# bicyclelab-charger-4_1.net
KiCad netlist of a schematic drawn in EAGLE
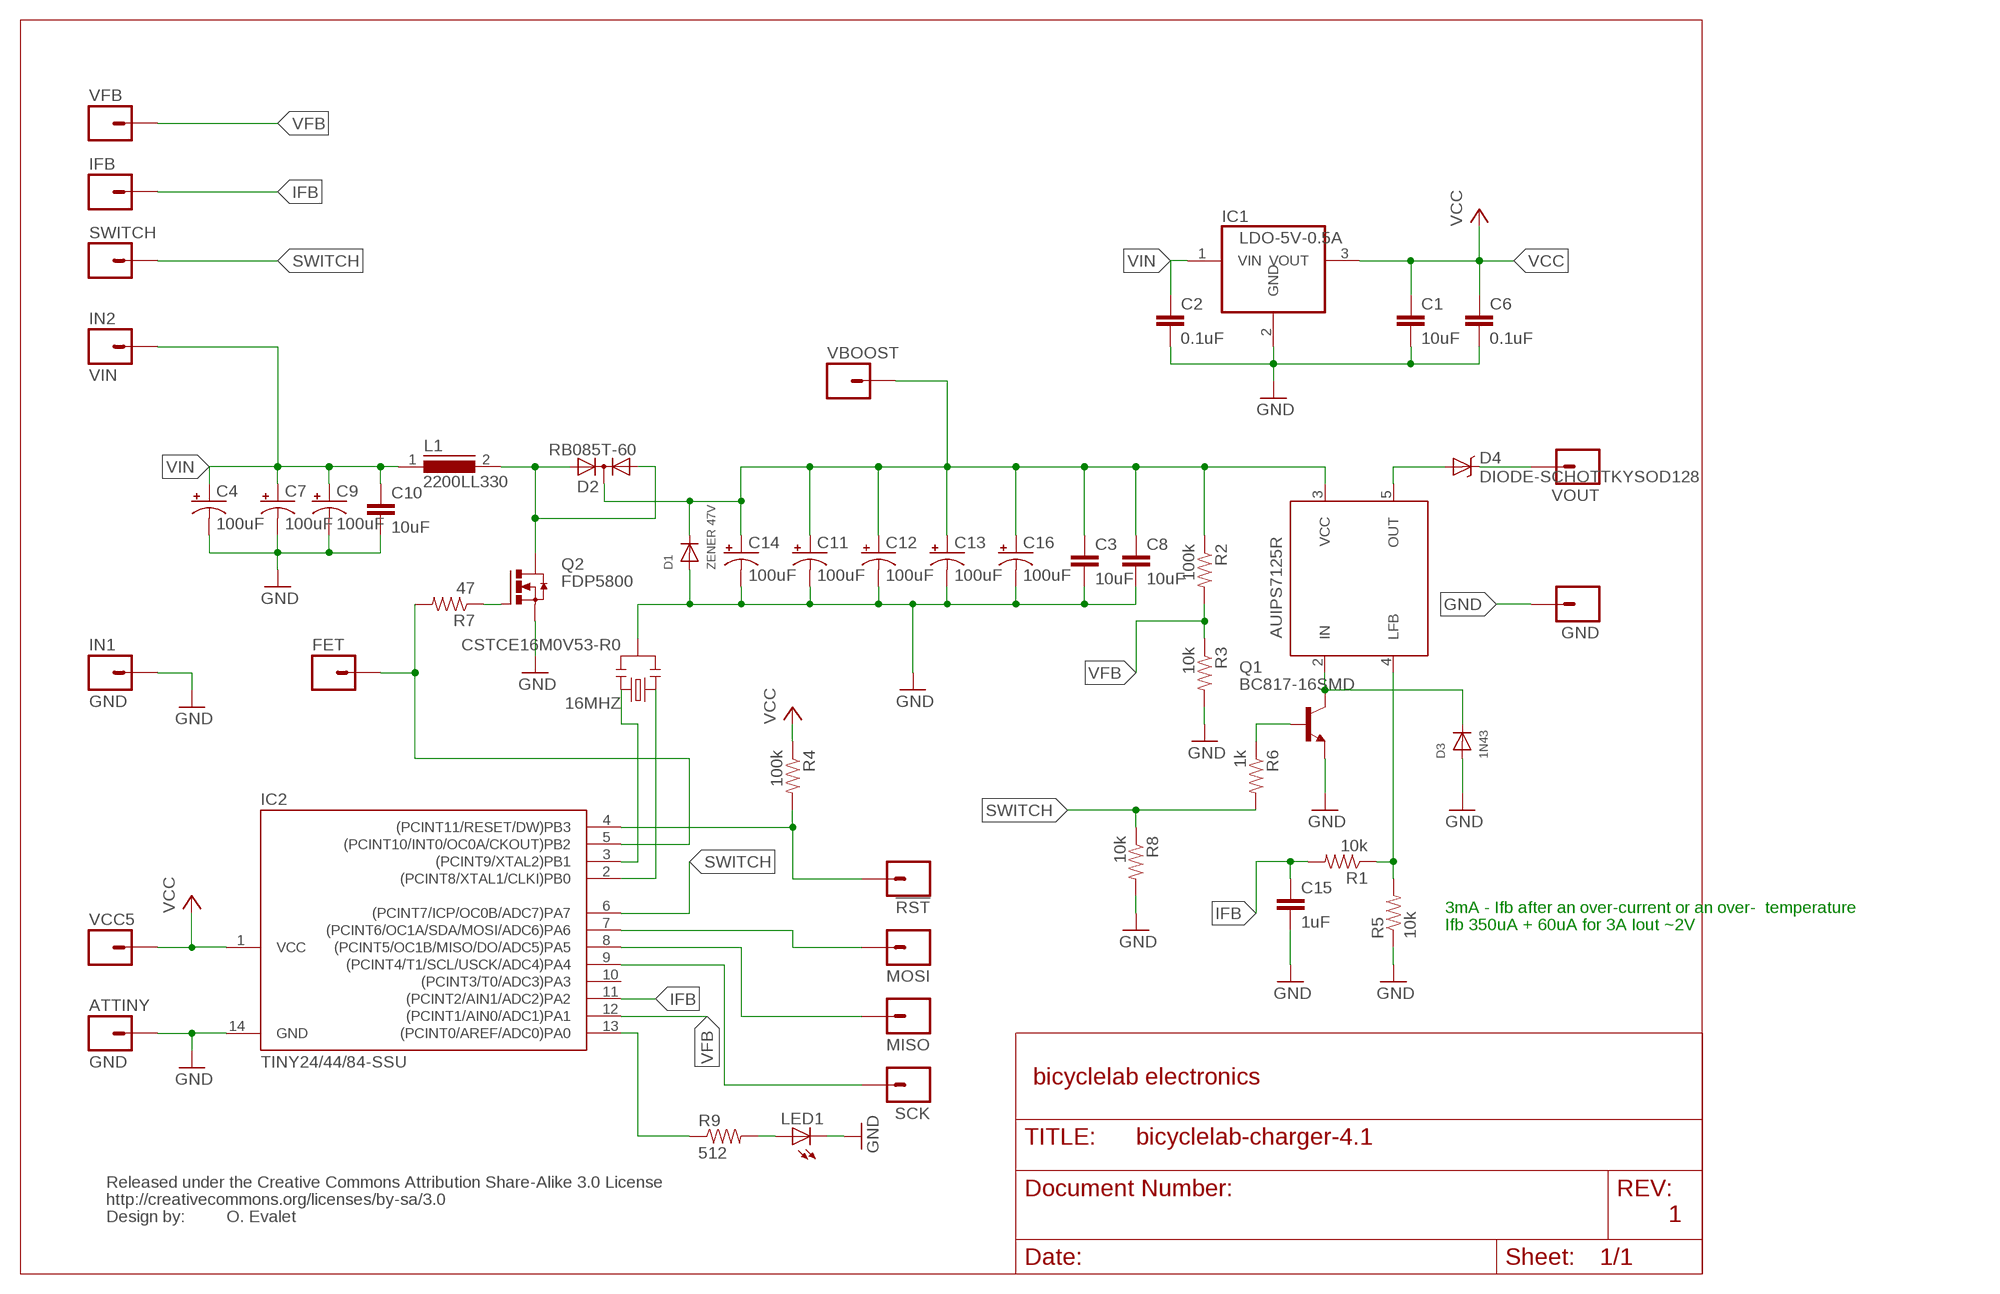
[diagram p0: schematic, sheet 1]

(export (version "E")
  (design (tool "Eeschema 10.0.6"))
  (components
    (comp (ref "!RST")
      (value "M01SMDNS")
      (footprint "eagle-import:1X01NS")
      (libsource (lib "eagle-import") (part "M01SMDNS"))
    )
    (comp (ref "16MHZ")
      (value "CSTCE16M0V53-R0")
      (footprint "eagle-import:RESONATOR-SMD")
      (libsource (lib "eagle-import") (part "RESONATORSMD"))
    )
    (comp (ref "ATTINY")
      (value "GND")
      (footprint "eagle-import:1X01NS")
      (libsource (lib "eagle-import") (part "M01SMDNS"))
    )
    (comp (ref "C1")
      (value "10uF")
      (footprint "eagle-import:0805")
      (libsource (lib "eagle-import") (part "bicyclelab_CAP0805"))
    )
    (comp (ref "C2")
      (value "0.1uF")
      (footprint "eagle-import:0805")
      (libsource (lib "eagle-import") (part "CAP0805"))
    )
    (comp (ref "C3")
      (value "10uF")
      (footprint "eagle-import:1210")
      (libsource (lib "eagle-import") (part "CAP1210"))
    )
    (comp (ref "C4")
      (value "100uF")
      (footprint "eagle-import:PANASONIC_D")
      (libsource (lib "eagle-import") (part "CPOL-USD"))
    )
    (comp (ref "C6")
      (value "0.1uF")
      (footprint "eagle-import:0805")
      (libsource (lib "eagle-import") (part "CAP0805"))
    )
    (comp (ref "C7")
      (value "100uF")
      (footprint "eagle-import:PANASONIC_D")
      (libsource (lib "eagle-import") (part "CPOL-USD"))
    )
    (comp (ref "C8")
      (value "10uF")
      (footprint "eagle-import:1210")
      (libsource (lib "eagle-import") (part "CAP1210"))
    )
    (comp (ref "C9")
      (value "100uF")
      (footprint "eagle-import:PANASONIC_D")
      (libsource (lib "eagle-import") (part "CPOL-USD"))
    )
    (comp (ref "C10")
      (value "10uF")
      (footprint "eagle-import:1210")
      (libsource (lib "eagle-import") (part "CAP1210"))
    )
    (comp (ref "C11")
      (value "100uF")
      (footprint "eagle-import:PANASONIC_D")
      (libsource (lib "eagle-import") (part "CPOL-USD"))
    )
    (comp (ref "C12")
      (value "100uF")
      (footprint "eagle-import:PANASONIC_D")
      (libsource (lib "eagle-import") (part "CPOL-USD"))
    )
    (comp (ref "C13")
      (value "100uF")
      (footprint "eagle-import:PANASONIC_D")
      (libsource (lib "eagle-import") (part "CPOL-USD"))
    )
    (comp (ref "C14")
      (value "100uF")
      (footprint "eagle-import:PANASONIC_D")
      (libsource (lib "eagle-import") (part "CPOL-USD"))
    )
    (comp (ref "C15")
      (value "1uF")
      (footprint "eagle-import:0805")
      (libsource (lib "eagle-import") (part "CAP0805"))
    )
    (comp (ref "C16")
      (value "100uF")
      (footprint "eagle-import:PANASONIC_D")
      (libsource (lib "eagle-import") (part "CPOL-USD"))
    )
    (comp (ref "D1")
      (value "ZENER 47V")
      (footprint "eagle-import:SOD-123")
      (libsource (lib "eagle-import") (part "DIODESOD-123"))
    )
    (comp (ref "D2")
      (value "RB085T-60")
      (footprint "eagle-import:TO220AB")
      (libsource (lib "eagle-import") (part "DIODE-2AC|CATO220H"))
    )
    (comp (ref "D3")
      (value "1N43")
      (footprint "eagle-import:SOD-123")
      (libsource (lib "eagle-import") (part "DIODESOD-123"))
    )
    (comp (ref "D4")
      (value "DIODE-SCHOTTKYSOD128")
      (footprint "eagle-import:SOD-128")
      (libsource (lib "eagle-import") (part "DIODE-SCHOTTKYSOD128"))
    )
    (comp (ref "FET")
      (value "M01SMDNS")
      (footprint "eagle-import:1X01NS")
      (libsource (lib "eagle-import") (part "M01SMDNS"))
    )
    (comp (ref "GND")
      (value "M01SMDNS")
      (footprint "eagle-import:1X01NS")
      (libsource (lib "eagle-import") (part "M01SMDNS"))
    )
    (comp (ref "IC1")
      (value "LDO-5V-0.5A")
      (footprint "eagle-import:SOT223")
      (libsource (lib "eagle-import") (part "LDO-5V-0.5A"))
    )
    (comp (ref "IC2")
      (value "TINY24/44/84-SSU")
      (footprint "eagle-import:SOIC14")
      (libsource (lib "eagle-import") (part "TINY24/44/84-SSU"))
    )
    (comp (ref "IFB")
      (value "M01SMDNS")
      (footprint "eagle-import:1X01NS")
      (libsource (lib "eagle-import") (part "M01SMDNS"))
    )
    (comp (ref "IN1")
      (value "GND")
      (footprint "eagle-import:1X01NS")
      (libsource (lib "eagle-import") (part "M01SMDNS"))
    )
    (comp (ref "IN2")
      (value "VIN")
      (footprint "eagle-import:1X01")
      (libsource (lib "eagle-import") (part "M01PTH"))
    )
    (comp (ref "L1")
      (value "2200LL330")
      (footprint "eagle-import:DR175")
      (libsource (lib "eagle-import") (part "DR175"))
    )
    (comp (ref "LED1")
      (value "LEDCHIP-LED0805")
      (footprint "eagle-import:CHIP-LED0805")
      (libsource (lib "eagle-import") (part "LEDCHIP-LED0805"))
    )
    (comp (ref "MISO")
      (value "M01SMDNS")
      (footprint "eagle-import:1X01NS")
      (libsource (lib "eagle-import") (part "M01SMDNS"))
    )
    (comp (ref "MOSI")
      (value "M01SMDNS")
      (footprint "eagle-import:1X01NS")
      (libsource (lib "eagle-import") (part "M01SMDNS"))
    )
    (comp (ref "Q1")
      (value "BC817-16SMD")
      (footprint "eagle-import:SOT23-BEC")
      (libsource (lib "eagle-import") (part "BC817SMD-16"))
    )
    (comp (ref "Q2")
      (value "FDP5800")
      (footprint "eagle-import:TO220AH")
      (libsource (lib "eagle-import") (part "IRF3704"))
    )
    (comp (ref "R1")
      (value "10k")
      (footprint "eagle-import:0805")
      (libsource (lib "eagle-import") (part "RESISTOR"))
    )
    (comp (ref "R2")
      (value "100k")
      (footprint "eagle-import:0805")
      (libsource (lib "eagle-import") (part "RESISTOR"))
    )
    (comp (ref "R3")
      (value "10k")
      (footprint "eagle-import:0805")
      (libsource (lib "eagle-import") (part "RESISTOR"))
    )
    (comp (ref "R4")
      (value "100k")
      (footprint "eagle-import:0805")
      (libsource (lib "eagle-import") (part "RESISTOR"))
    )
    (comp (ref "R5")
      (value "10k")
      (footprint "eagle-import:0805")
      (libsource (lib "eagle-import") (part "RESISTOR"))
    )
    (comp (ref "R6")
      (value "1k")
      (footprint "eagle-import:0805")
      (libsource (lib "eagle-import") (part "RESISTOR"))
    )
    (comp (ref "R7")
      (value "47")
      (footprint "eagle-import:0805")
      (libsource (lib "eagle-import") (part "RESISTOR"))
    )
    (comp (ref "R8")
      (value "10k")
      (footprint "eagle-import:0805")
      (libsource (lib "eagle-import") (part "RESISTOR"))
    )
    (comp (ref "R9")
      (value "512")
      (footprint "eagle-import:0805")
      (libsource (lib "eagle-import") (part "RESISTOR"))
    )
    (comp (ref "SCK")
      (value "M01SMDNS")
      (footprint "eagle-import:1X01NS")
      (libsource (lib "eagle-import") (part "M01SMDNS"))
    )
    (comp (ref "SWITCH")
      (value "M01SMDNS")
      (footprint "eagle-import:1X01NS")
      (libsource (lib "eagle-import") (part "M01SMDNS"))
    )
    (comp (ref "U$5")
      (value "CREATIVE_COMMONS")
      (footprint "eagle-import:CREATIVE_COMMONS")
      (libsource (lib "eagle-import") (part "CREATIVE_COMMONS"))
    )
    (comp (ref "U$8")
      (value "AUIPS7125R")
      (footprint "eagle-import:DPAK-5")
      (libsource (lib "eagle-import") (part "AUIPS7125R"))
    )
    (comp (ref "VBOOST")
      (value "M01SMDNS")
      (footprint "eagle-import:1X01NS")
      (libsource (lib "eagle-import") (part "M01SMDNS"))
    )
    (comp (ref "VCC5")
      (value "M01PTH")
      (footprint "eagle-import:1X01")
      (libsource (lib "eagle-import") (part "M01PTH"))
    )
    (comp (ref "VFB")
      (value "M01SMDNS")
      (footprint "eagle-import:1X01NS")
      (libsource (lib "eagle-import") (part "M01SMDNS"))
    )
    (comp (ref "VOUT")
      (value "M01PTH")
      (footprint "eagle-import:1X01")
      (libsource (lib "eagle-import") (part "M01PTH"))
    )
  )
  (nets
    (net (code "1") (name "GND") (class "Default")
      (node (ref "16MHZ") (pin "2") (pinfunction "2_2") (pintype "passive"))
      (node (ref "ATTINY") (pin "1") (pinfunction "1_1") (pintype "passive"))
      (node (ref "C1") (pin "2") (pinfunction "2_2") (pintype "passive"))
      (node (ref "C10") (pin "2") (pinfunction "2_2") (pintype "passive"))
      (node (ref "C11") (pin "-") (pinfunction "-_-") (pintype "passive"))
      (node (ref "C12") (pin "-") (pinfunction "-_-") (pintype "passive"))
      (node (ref "C13") (pin "-") (pinfunction "-_-") (pintype "passive"))
      (node (ref "C14") (pin "-") (pinfunction "-_-") (pintype "passive"))
      (node (ref "C15") (pin "2") (pinfunction "2_2") (pintype "passive"))
      (node (ref "C16") (pin "-") (pinfunction "-_-") (pintype "passive"))
      (node (ref "C2") (pin "2") (pinfunction "2_2") (pintype "passive"))
      (node (ref "C3") (pin "2") (pinfunction "2_2") (pintype "passive"))
      (node (ref "C4") (pin "-") (pinfunction "-_-") (pintype "passive"))
      (node (ref "C6") (pin "2") (pinfunction "2_2") (pintype "passive"))
      (node (ref "C7") (pin "-") (pinfunction "-_-") (pintype "passive"))
      (node (ref "C8") (pin "2") (pinfunction "2_2") (pintype "passive"))
      (node (ref "C9") (pin "-") (pinfunction "-_-") (pintype "passive"))
      (node (ref "D1") (pin "A") (pinfunction "A_A") (pintype "passive"))
      (node (ref "D3") (pin "A") (pinfunction "A_A") (pintype "passive"))
      (node (ref "GND") (pin "1") (pinfunction "1_1") (pintype "passive"))
      (node (ref "IC1") (pin "2") (pinfunction "GND_2") (pintype "power_in"))
      (node (ref "IC2") (pin "14") (pinfunction "GND_14") (pintype "power_in"))
      (node (ref "IN1") (pin "1") (pinfunction "1_1") (pintype "passive"))
      (node (ref "LED1") (pin "C") (pinfunction "C_C") (pintype "passive"))
      (node (ref "Q1") (pin "E") (pinfunction "E_E") (pintype "passive"))
      (node (ref "Q2") (pin "E") (pinfunction "S_E") (pintype "passive"))
      (node (ref "R3") (pin "2") (pinfunction "2_2") (pintype "passive"))
      (node (ref "R5") (pin "1") (pinfunction "1_1") (pintype "passive"))
      (node (ref "R8") (pin "2") (pinfunction "2_2") (pintype "passive"))
    )
    (net (code "2") (name "IFB") (class "Default")
      (node (ref "C15") (pin "1") (pinfunction "1_1") (pintype "passive"))
      (node (ref "IC2") (pin "11") (pinfunction "(PCINT2/AIN1/ADC2)PA2_11") (pintype "bidirectional"))
      (node (ref "IFB") (pin "1") (pinfunction "1_1") (pintype "passive"))
      (node (ref "R1") (pin "2") (pinfunction "2_2") (pintype "passive"))
    )
    (net (code "3") (name "Net-(D4-A)") (class "Default")
      (node (ref "D4") (pin "2") (pinfunction "A_2") (pintype "passive"))
      (node (ref "U$8") (pin "5") (pinfunction "OUT_5") (pintype "output"))
    )
    (net (code "4") (name "Net-(D4-C)") (class "Default")
      (node (ref "D4") (pin "1") (pinfunction "C_1") (pintype "passive"))
      (node (ref "VOUT") (pin "1") (pinfunction "1_1") (pintype "passive"))
    )
    (net (code "5") (name "Net-(IC2-(PCINT0{slash}AREF{slash}ADC0)PA0)") (class "Default")
      (node (ref "IC2") (pin "13") (pinfunction "(PCINT0/AREF/ADC0)PA0_13") (pintype "bidirectional"))
      (node (ref "R9") (pin "1") (pinfunction "1_1") (pintype "passive"))
    )
    (net (code "6") (name "Net-(IC2-(PCINT4{slash}T1{slash}SCL{slash}USCK{slash}ADC4)PA4)") (class "Default")
      (node (ref "IC2") (pin "9") (pinfunction "(PCINT4/T1/SCL/USCK/ADC4)PA4_9") (pintype "bidirectional"))
      (node (ref "SCK") (pin "1") (pinfunction "1_1") (pintype "passive"))
    )
    (net (code "7") (name "Net-(IC2-(PCINT5{slash}OC1B{slash}MISO{slash}DO{slash}ADC5)PA5)") (class "Default")
      (node (ref "IC2") (pin "8") (pinfunction "(PCINT5/OC1B/MISO/DO/ADC5)PA5_8") (pintype "bidirectional"))
      (node (ref "MISO") (pin "1") (pinfunction "1_1") (pintype "passive"))
    )
    (net (code "8") (name "Net-(IC2-(PCINT6{slash}OC1A{slash}SDA{slash}MOSI{slash}ADC6)PA6)") (class "Default")
      (node (ref "IC2") (pin "7") (pinfunction "(PCINT6/OC1A/SDA/MOSI/ADC6)PA6_7") (pintype "bidirectional"))
      (node (ref "MOSI") (pin "1") (pinfunction "1_1") (pintype "passive"))
    )
    (net (code "9") (name "Net-(IC2-(PCINT8{slash}XTAL1{slash}CLKI)PB0)") (class "Default")
      (node (ref "16MHZ") (pin "1") (pinfunction "1_1") (pintype "passive"))
      (node (ref "IC2") (pin "2") (pinfunction "(PCINT8/XTAL1/CLKI)PB0_2") (pintype "bidirectional"))
    )
    (net (code "10") (name "Net-(IC2-(PCINT9{slash}XTAL2)PB1)") (class "Default")
      (node (ref "16MHZ") (pin "3") (pinfunction "3_3") (pintype "passive"))
      (node (ref "IC2") (pin "3") (pinfunction "(PCINT9/XTAL2)PB1_3") (pintype "bidirectional"))
    )
    (net (code "11") (name "Net-(IC2-(PCINT10{slash}INT0{slash}OC0A{slash}CKOUT)PB2)") (class "Default")
      (node (ref "FET") (pin "1") (pinfunction "1_1") (pintype "passive"))
      (node (ref "IC2") (pin "5") (pinfunction "(PCINT10/INT0/OC0A/CKOUT)PB2_5") (pintype "bidirectional"))
      (node (ref "R7") (pin "2") (pinfunction "2_2") (pintype "passive"))
    )
    (net (code "12") (name "Net-(IC2-(PCINT11{slash}RESET{slash}DW)PB3)") (class "Default")
      (node (ref "!RST") (pin "1") (pinfunction "1_1") (pintype "passive"))
      (node (ref "IC2") (pin "4") (pinfunction "(PCINT11/RESET/DW)PB3_4") (pintype "bidirectional"))
      (node (ref "R4") (pin "2") (pinfunction "2_2") (pintype "passive"))
    )
    (net (code "13") (name "Net-(LED1-PadA)") (class "Default")
      (node (ref "LED1") (pin "A") (pinfunction "A_A") (pintype "passive"))
      (node (ref "R9") (pin "2") (pinfunction "2_2") (pintype "passive"))
    )
    (net (code "14") (name "Net-(Q1-PadB)") (class "Default")
      (node (ref "Q1") (pin "B") (pinfunction "B_B") (pintype "passive"))
      (node (ref "R6") (pin "1") (pinfunction "1_1") (pintype "passive"))
    )
    (net (code "15") (name "Net-(Q2-D)") (class "Default")
      (node (ref "D2") (pin "A1") (pinfunction "A1_A1") (pintype "passive"))
      (node (ref "D2") (pin "A2") (pinfunction "A2_A2") (pintype "passive"))
      (node (ref "L1") (pin "2") (pinfunction "2_2") (pintype "passive"))
      (node (ref "Q2") (pin "C") (pinfunction "D_C") (pintype "passive"))
    )
    (net (code "16") (name "Net-(Q2-G)") (class "Default")
      (node (ref "Q2") (pin "B") (pinfunction "G_B") (pintype "passive"))
      (node (ref "R7") (pin "1") (pinfunction "1_1") (pintype "passive"))
    )
    (net (code "17") (name "Net-(U$8-IN)") (class "Default")
      (node (ref "D3") (pin "C") (pinfunction "C_C") (pintype "passive"))
      (node (ref "Q1") (pin "C") (pinfunction "C_C") (pintype "passive"))
      (node (ref "U$8") (pin "2") (pinfunction "IN_2") (pintype "input"))
    )
    (net (code "18") (name "Net-(U$8-LFB)") (class "Default")
      (node (ref "R1") (pin "1") (pinfunction "1_1") (pintype "passive"))
      (node (ref "R5") (pin "2") (pinfunction "2_2") (pintype "passive"))
      (node (ref "U$8") (pin "4") (pinfunction "LFB_4") (pintype "output"))
    )
    (net (code "19") (name "Net-(U$8-VCC)") (class "Default")
      (node (ref "C11") (pin "+") (pinfunction "+_+") (pintype "passive"))
      (node (ref "C12") (pin "+") (pinfunction "+_+") (pintype "passive"))
      (node (ref "C13") (pin "+") (pinfunction "+_+") (pintype "passive"))
      (node (ref "C14") (pin "+") (pinfunction "+_+") (pintype "passive"))
      (node (ref "C16") (pin "+") (pinfunction "+_+") (pintype "passive"))
      (node (ref "C3") (pin "1") (pinfunction "1_1") (pintype "passive"))
      (node (ref "C8") (pin "1") (pinfunction "1_1") (pintype "passive"))
      (node (ref "D1") (pin "C") (pinfunction "C_C") (pintype "passive"))
      (node (ref "D2") (pin "C") (pinfunction "C_C") (pintype "passive"))
      (node (ref "R2") (pin "1") (pinfunction "1_1") (pintype "passive"))
      (node (ref "U$8") (pin "3") (pinfunction "VCC_3") (pintype "input"))
      (node (ref "VBOOST") (pin "1") (pinfunction "1_1") (pintype "passive"))
    )
    (net (code "20") (name "SWITCH") (class "Default")
      (node (ref "IC2") (pin "6") (pinfunction "(PCINT7/ICP/OC0B/ADC7)PA7_6") (pintype "bidirectional"))
      (node (ref "R6") (pin "2") (pinfunction "2_2") (pintype "passive"))
      (node (ref "R8") (pin "1") (pinfunction "1_1") (pintype "passive"))
      (node (ref "SWITCH") (pin "1") (pinfunction "1_1") (pintype "passive"))
    )
    (net (code "21") (name "VCC") (class "Default")
      (node (ref "C1") (pin "1") (pinfunction "1_1") (pintype "passive"))
      (node (ref "C6") (pin "1") (pinfunction "1_1") (pintype "passive"))
      (node (ref "IC1") (pin "3") (pinfunction "VOUT_3") (pintype "output"))
      (node (ref "IC2") (pin "1") (pinfunction "VCC_1") (pintype "power_in"))
      (node (ref "R4") (pin "1") (pinfunction "1_1") (pintype "passive"))
      (node (ref "VCC5") (pin "1") (pinfunction "1_1") (pintype "passive"))
    )
    (net (code "22") (name "VFB") (class "Default")
      (node (ref "IC2") (pin "12") (pinfunction "(PCINT1/AIN0/ADC1)PA1_12") (pintype "bidirectional"))
      (node (ref "R2") (pin "2") (pinfunction "2_2") (pintype "passive"))
      (node (ref "R3") (pin "1") (pinfunction "1_1") (pintype "passive"))
      (node (ref "VFB") (pin "1") (pinfunction "1_1") (pintype "passive"))
    )
    (net (code "23") (name "VIN") (class "Default")
      (node (ref "C10") (pin "1") (pinfunction "1_1") (pintype "passive"))
      (node (ref "C2") (pin "1") (pinfunction "1_1") (pintype "passive"))
      (node (ref "C4") (pin "+") (pinfunction "+_+") (pintype "passive"))
      (node (ref "C7") (pin "+") (pinfunction "+_+") (pintype "passive"))
      (node (ref "C9") (pin "+") (pinfunction "+_+") (pintype "passive"))
      (node (ref "IC1") (pin "1") (pinfunction "VIN_1") (pintype "input"))
      (node (ref "IN2") (pin "1") (pinfunction "1_1") (pintype "passive"))
      (node (ref "L1") (pin "1") (pinfunction "1_1") (pintype "passive"))
    )
    (net (code "24") (name "unconnected-(IC2-(PCINT3{slash}T0{slash}ADC3)PA3-Pad10)") (class "Default")
      (node (ref "IC2") (pin "10") (pinfunction "(PCINT3/T0/ADC3)PA3_10") (pintype "bidirectional"))
    )
    (net (code "25") (name "unconnected-(U$8-NC-Pad1)") (class "Default")
      (node (ref "U$8") (pin "1") (pinfunction "NC_1") (pintype "no_connect"))
    )
  )
)
